# seismometer_potboard.net
KiCad netlist of a schematic drawn in EAGLE
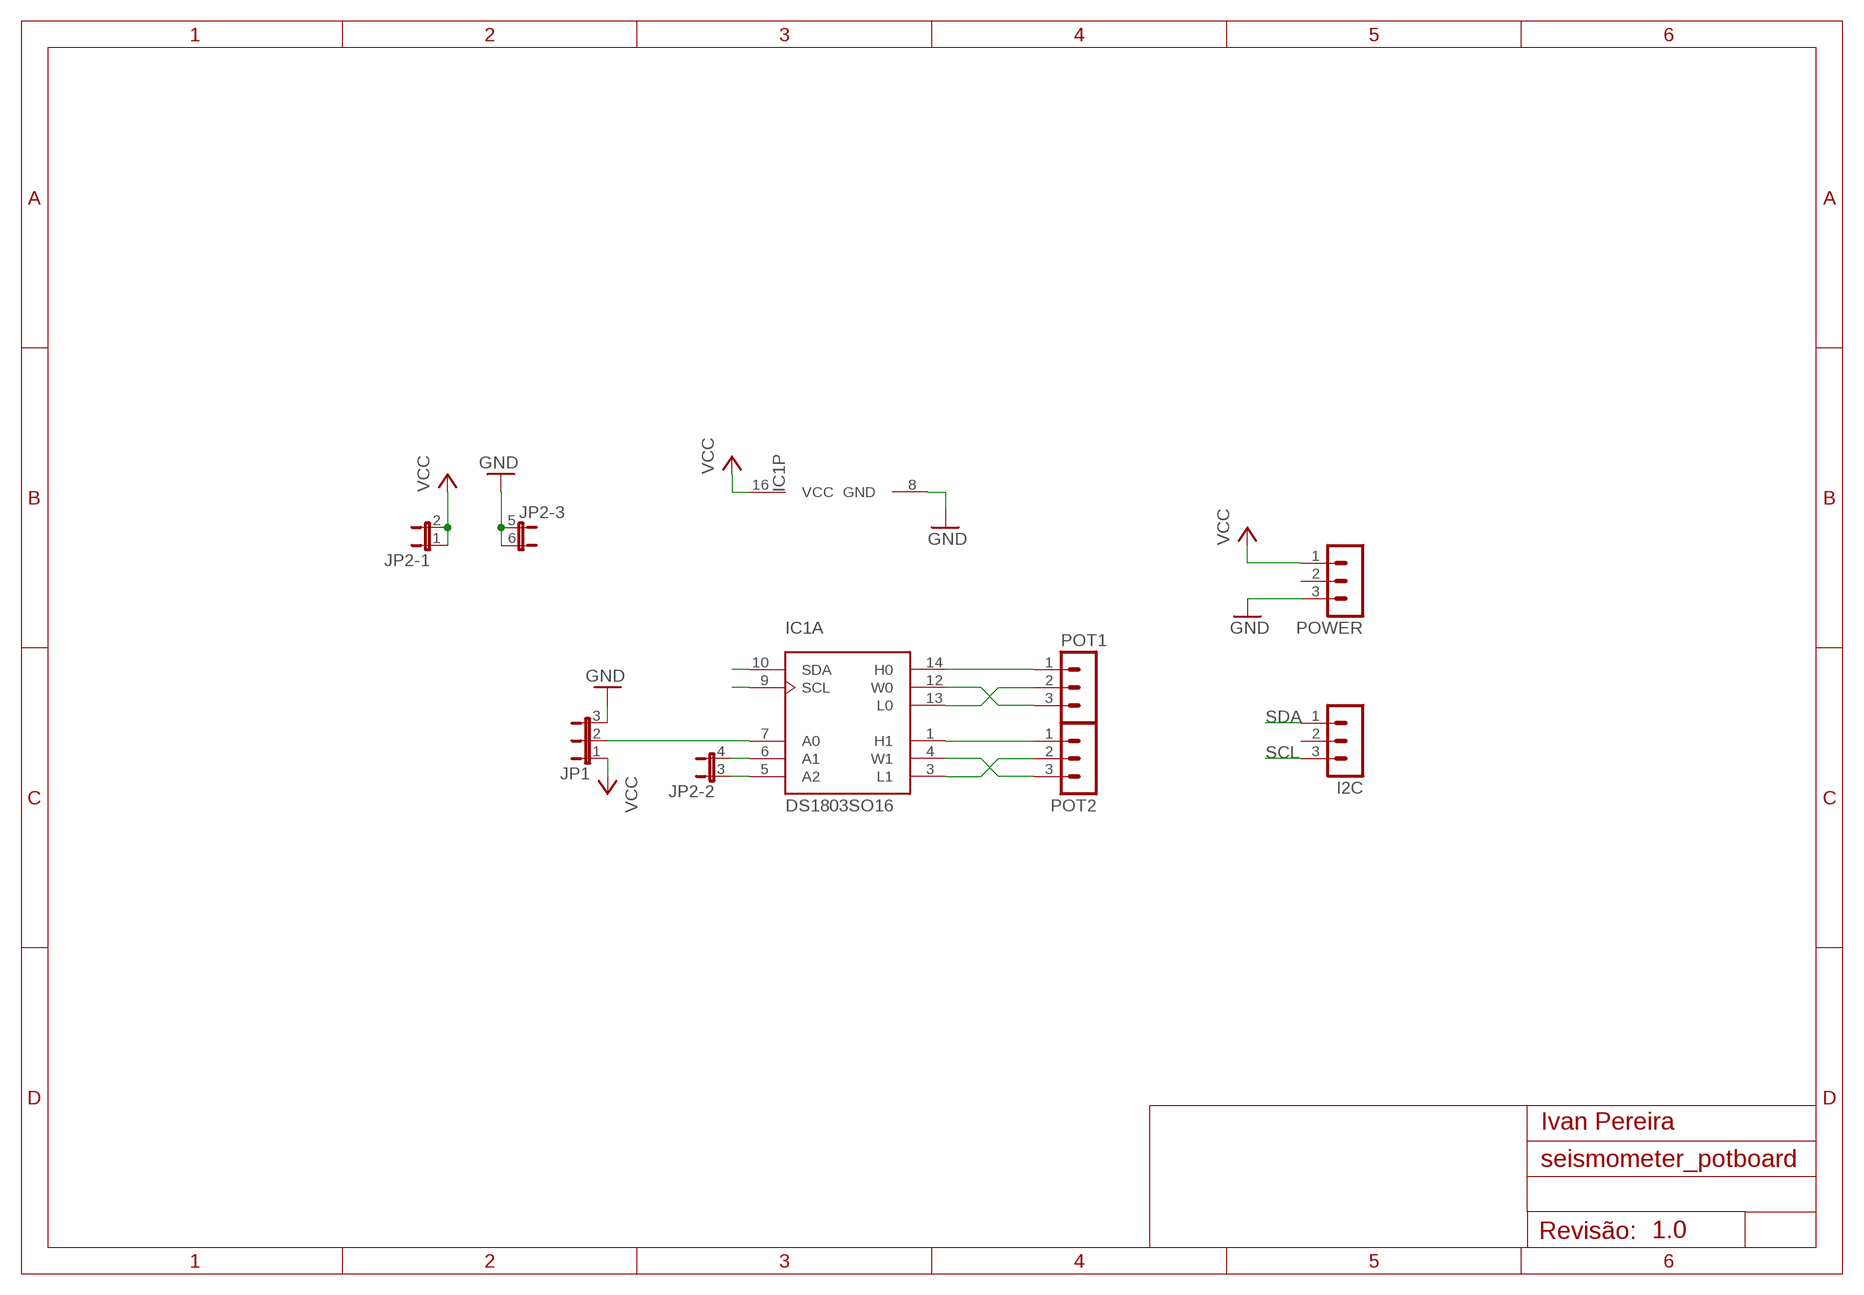
[diagram p0: schematic, sheet 1]

(export (version "E")
  (design (tool "Eeschema 10.0.6"))
  (components
    (comp (ref "I2C")
      (value "MA03-1")
      (footprint "eagle-import:MA03-1")
      (libsource (lib "eagle-import") (part "MA03-1"))
    )
    (comp (ref "IC1")
      (value "DS1803SO16")
      (footprint "eagle-import:SO16")
      (libsource (lib "eagle-import") (part "DS1803?SO16"))
    )
    (comp (ref "JP1")
      (value "JP2E")
      (footprint "eagle-import:JP2")
      (libsource (lib "eagle-import") (part "JP2E"))
    )
    (comp (ref "JP2")
      (value "JP3QE")
      (footprint "eagle-import:JP3Q")
      (libsource (lib "eagle-import") (part "JP3QE"))
    )
    (comp (ref "POT1")
      (value "MA03-1")
      (footprint "eagle-import:MA03-1")
      (libsource (lib "eagle-import") (part "MA03-1"))
    )
    (comp (ref "POT2")
      (value "MA03-1")
      (footprint "eagle-import:MA03-1")
      (libsource (lib "eagle-import") (part "MA03-1"))
    )
    (comp (ref "POWER")
      (value "MA03-1")
      (footprint "eagle-import:MA03-1")
      (libsource (lib "eagle-import") (part "MA03-1"))
    )
  )
  (nets
    (net (code "1") (name "/SCL") (class "Default")
      (node (ref "I2C") (pin "3") (pinfunction "3_3") (pintype "passive"))
      (node (ref "IC1") (pin "9") (pinfunction "SCL_9") (pintype "input"))
    )
    (net (code "2") (name "/SDA") (class "Default")
      (node (ref "I2C") (pin "1") (pinfunction "1_1") (pintype "passive"))
      (node (ref "IC1") (pin "10") (pinfunction "SDA_10") (pintype "bidirectional"))
    )
    (net (code "3") (name "GND") (class "Default")
      (node (ref "IC1") (pin "8") (pinfunction "GND_8") (pintype "power_in"))
      (node (ref "JP1") (pin "3") (pinfunction "3_3") (pintype "passive"))
      (node (ref "JP2") (pin "5") (pinfunction "1_5") (pintype "passive"))
      (node (ref "JP2") (pin "6") (pinfunction "2_6") (pintype "passive"))
      (node (ref "POWER") (pin "3") (pinfunction "3_3") (pintype "passive"))
    )
    (net (code "4") (name "Net-(IC1A-A0)") (class "Default")
      (node (ref "IC1") (pin "7") (pinfunction "A0_7") (pintype "input"))
      (node (ref "JP1") (pin "2") (pinfunction "2_2") (pintype "passive"))
    )
    (net (code "5") (name "Net-(IC1A-A1)") (class "Default")
      (node (ref "IC1") (pin "6") (pinfunction "A1_6") (pintype "input"))
      (node (ref "JP2") (pin "4") (pinfunction "2_4") (pintype "passive"))
    )
    (net (code "6") (name "Net-(IC1A-A2)") (class "Default")
      (node (ref "IC1") (pin "5") (pinfunction "A2_5") (pintype "input"))
      (node (ref "JP2") (pin "3") (pinfunction "1_3") (pintype "passive"))
    )
    (net (code "7") (name "Net-(IC1A-H0)") (class "Default")
      (node (ref "IC1") (pin "14") (pinfunction "H0_14") (pintype "bidirectional"))
      (node (ref "POT1") (pin "1") (pinfunction "1_1") (pintype "passive"))
    )
    (net (code "8") (name "Net-(IC1A-H1)") (class "Default")
      (node (ref "IC1") (pin "1") (pinfunction "H1_1") (pintype "bidirectional"))
      (node (ref "POT2") (pin "1") (pinfunction "1_1") (pintype "passive"))
    )
    (net (code "9") (name "Net-(IC1A-L0)") (class "Default")
      (node (ref "IC1") (pin "13") (pinfunction "L0_13") (pintype "bidirectional"))
      (node (ref "POT1") (pin "2") (pinfunction "2_2") (pintype "passive"))
    )
    (net (code "10") (name "Net-(IC1A-L1)") (class "Default")
      (node (ref "IC1") (pin "3") (pinfunction "L1_3") (pintype "bidirectional"))
      (node (ref "POT2") (pin "2") (pinfunction "2_2") (pintype "passive"))
    )
    (net (code "11") (name "Net-(IC1A-W0)") (class "Default")
      (node (ref "IC1") (pin "12") (pinfunction "W0_12") (pintype "bidirectional"))
      (node (ref "POT1") (pin "3") (pinfunction "3_3") (pintype "passive"))
    )
    (net (code "12") (name "Net-(IC1A-W1)") (class "Default")
      (node (ref "IC1") (pin "4") (pinfunction "W1_4") (pintype "bidirectional"))
      (node (ref "POT2") (pin "3") (pinfunction "3_3") (pintype "passive"))
    )
    (net (code "13") (name "VCC") (class "Default")
      (node (ref "IC1") (pin "16") (pinfunction "VCC_16") (pintype "power_in"))
      (node (ref "JP1") (pin "1") (pinfunction "1_1") (pintype "passive"))
      (node (ref "JP2") (pin "1") (pinfunction "1_1") (pintype "passive"))
      (node (ref "JP2") (pin "2") (pinfunction "2_2") (pintype "passive"))
      (node (ref "POWER") (pin "1") (pinfunction "1_1") (pintype "passive"))
    )
    (net (code "14") (name "unconnected-(I2C-Pad2)") (class "Default")
      (node (ref "I2C") (pin "2") (pinfunction "2_2") (pintype "passive"))
    )
    (net (code "15") (name "unconnected-(POWER-Pad2)") (class "Default")
      (node (ref "POWER") (pin "2") (pinfunction "2_2") (pintype "passive"))
    )
  )
)
